# driver_fet.net
KiCad netlist of a schematic drawn in EAGLE
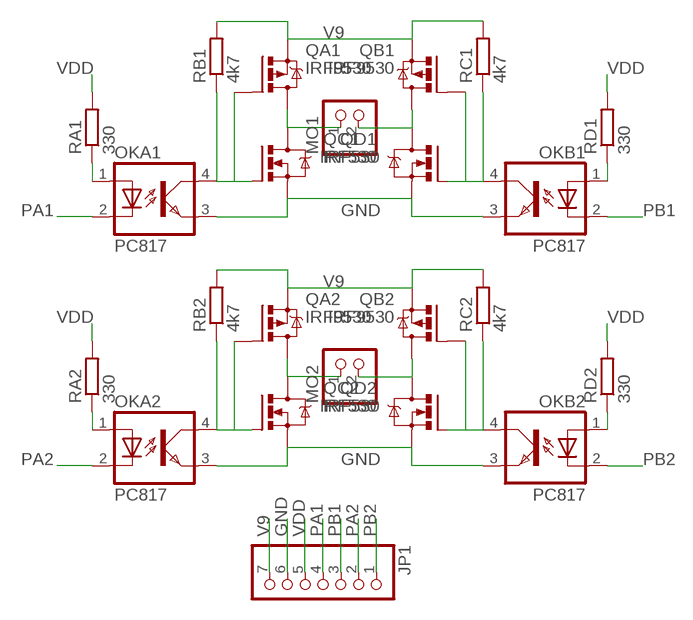
[diagram p0: schematic, sheet 1]

(export (version "E")
  (design (tool "Eeschema 10.0.6"))
  (components
    (comp (ref "JP1")
      (value "PINHD-1X7")
      (footprint "eagle-import:1X07")
      (libsource (lib "eagle-import") (part "PINHD-1X7"))
    )
    (comp (ref "MO1")
      (value "PINHD-1X2")
      (footprint "eagle-import:1X02")
      (libsource (lib "eagle-import") (part "PINHD-1X2"))
    )
    (comp (ref "MO2")
      (value "PINHD-1X2")
      (footprint "eagle-import:1X02")
      (libsource (lib "eagle-import") (part "PINHD-1X2"))
    )
    (comp (ref "OKA1")
      (value "PC817")
      (footprint "eagle-import:DIL04")
      (fields (field (name "MPN") "PC817X4J000F"))
      (libsource (lib "eagle-import") (part "PC817"))
    )
    (comp (ref "OKA2")
      (value "PC817")
      (footprint "eagle-import:DIL04")
      (fields (field (name "MPN") "PC817X4J000F"))
      (libsource (lib "eagle-import") (part "PC817"))
    )
    (comp (ref "OKB1")
      (value "PC817")
      (footprint "eagle-import:DIL04")
      (fields (field (name "MPN") "PC817X4J000F"))
      (libsource (lib "eagle-import") (part "PC817"))
    )
    (comp (ref "OKB2")
      (value "PC817")
      (footprint "eagle-import:DIL04")
      (fields (field (name "MPN") "PC817X4J000F"))
      (libsource (lib "eagle-import") (part "PC817"))
    )
    (comp (ref "QA1")
      (value "IRF9530")
      (footprint "eagle-import:TO220BV")
      (libsource (lib "eagle-import") (part "IRF9530"))
    )
    (comp (ref "QA2")
      (value "IRF9530")
      (footprint "eagle-import:TO220BV")
      (libsource (lib "eagle-import") (part "IRF9530"))
    )
    (comp (ref "QB1")
      (value "IRF9530")
      (footprint "eagle-import:TO220BV")
      (libsource (lib "eagle-import") (part "IRF9530"))
    )
    (comp (ref "QB2")
      (value "IRF9530")
      (footprint "eagle-import:TO220BV")
      (libsource (lib "eagle-import") (part "IRF9530"))
    )
    (comp (ref "QC1")
      (value "IRF530")
      (footprint "eagle-import:TO220BV")
      (libsource (lib "eagle-import") (part "IRF530"))
    )
    (comp (ref "QC2")
      (value "IRF530")
      (footprint "eagle-import:TO220BV")
      (libsource (lib "eagle-import") (part "IRF530"))
    )
    (comp (ref "QD1")
      (value "IRF530")
      (footprint "eagle-import:TO220BV")
      (libsource (lib "eagle-import") (part "IRF530"))
    )
    (comp (ref "QD2")
      (value "IRF530")
      (footprint "eagle-import:TO220BV")
      (libsource (lib "eagle-import") (part "IRF530"))
    )
    (comp (ref "RA1")
      (value "330")
      (footprint "eagle-import:R1206")
      (libsource (lib "eagle-import") (part "R-EU_R1206"))
    )
    (comp (ref "RA2")
      (value "330")
      (footprint "eagle-import:R1206")
      (libsource (lib "eagle-import") (part "R-EU_R1206"))
    )
    (comp (ref "RB1")
      (value "4k7")
      (footprint "eagle-import:R1206")
      (libsource (lib "eagle-import") (part "R-EU_R1206"))
    )
    (comp (ref "RB2")
      (value "4k7")
      (footprint "eagle-import:R1206")
      (libsource (lib "eagle-import") (part "R-EU_R1206"))
    )
    (comp (ref "RC1")
      (value "4k7")
      (footprint "eagle-import:R1206")
      (libsource (lib "eagle-import") (part "R-EU_R1206"))
    )
    (comp (ref "RC2")
      (value "4k7")
      (footprint "eagle-import:R1206")
      (libsource (lib "eagle-import") (part "R-EU_R1206"))
    )
    (comp (ref "RD1")
      (value "330")
      (footprint "eagle-import:R1206")
      (libsource (lib "eagle-import") (part "R-EU_R1206"))
    )
    (comp (ref "RD2")
      (value "330")
      (footprint "eagle-import:R1206")
      (libsource (lib "eagle-import") (part "R-EU_R1206"))
    )
  )
  (nets
    (net (code "1") (name "/GND") (class "Default")
      (node (ref "JP1") (pin "6") (pinfunction "6_6") (pintype "passive"))
      (node (ref "OKA1") (pin "3") (pinfunction "EMIT_3") (pintype "passive"))
      (node (ref "OKA2") (pin "3") (pinfunction "EMIT_3") (pintype "passive"))
      (node (ref "OKB1") (pin "3") (pinfunction "EMIT_3") (pintype "passive"))
      (node (ref "OKB2") (pin "3") (pinfunction "EMIT_3") (pintype "passive"))
      (node (ref "QC1") (pin "S") (pinfunction "S_S") (pintype "passive"))
      (node (ref "QC2") (pin "S") (pinfunction "S_S") (pintype "passive"))
      (node (ref "QD1") (pin "S") (pinfunction "S_S") (pintype "passive"))
      (node (ref "QD2") (pin "S") (pinfunction "S_S") (pintype "passive"))
    )
    (net (code "2") (name "/PA1") (class "Default")
      (node (ref "JP1") (pin "4") (pinfunction "4_4") (pintype "passive"))
      (node (ref "OKA1") (pin "2") (pinfunction "C_2") (pintype "passive"))
    )
    (net (code "3") (name "/PA2") (class "Default")
      (node (ref "JP1") (pin "2") (pinfunction "2_2") (pintype "passive"))
      (node (ref "OKA2") (pin "2") (pinfunction "C_2") (pintype "passive"))
    )
    (net (code "4") (name "/PB1") (class "Default")
      (node (ref "JP1") (pin "3") (pinfunction "3_3") (pintype "passive"))
      (node (ref "OKB1") (pin "2") (pinfunction "C_2") (pintype "passive"))
    )
    (net (code "5") (name "/PB2") (class "Default")
      (node (ref "JP1") (pin "1") (pinfunction "1_1") (pintype "passive"))
      (node (ref "OKB2") (pin "2") (pinfunction "C_2") (pintype "passive"))
    )
    (net (code "6") (name "/V9") (class "Default")
      (node (ref "JP1") (pin "7") (pinfunction "7_7") (pintype "passive"))
      (node (ref "QA1") (pin "S") (pinfunction "S_S") (pintype "passive"))
      (node (ref "QA2") (pin "S") (pinfunction "S_S") (pintype "passive"))
      (node (ref "QB1") (pin "S") (pinfunction "S_S") (pintype "passive"))
      (node (ref "QB2") (pin "S") (pinfunction "S_S") (pintype "passive"))
      (node (ref "RB1") (pin "2") (pinfunction "2_2") (pintype "passive"))
      (node (ref "RB2") (pin "2") (pinfunction "2_2") (pintype "passive"))
      (node (ref "RC1") (pin "2") (pinfunction "2_2") (pintype "passive"))
      (node (ref "RC2") (pin "2") (pinfunction "2_2") (pintype "passive"))
    )
    (net (code "7") (name "/VDD") (class "Default")
      (node (ref "JP1") (pin "5") (pinfunction "5_5") (pintype "passive"))
      (node (ref "RA1") (pin "2") (pinfunction "2_2") (pintype "passive"))
      (node (ref "RA2") (pin "2") (pinfunction "2_2") (pintype "passive"))
      (node (ref "RD1") (pin "2") (pinfunction "2_2") (pintype "passive"))
      (node (ref "RD2") (pin "2") (pinfunction "2_2") (pintype "passive"))
    )
    (net (code "8") (name "Net-(MO1-Pad1)") (class "Default")
      (node (ref "MO1") (pin "1") (pinfunction "1_1") (pintype "passive"))
      (node (ref "QA1") (pin "D") (pinfunction "D_D") (pintype "passive"))
      (node (ref "QC1") (pin "D") (pinfunction "D_D") (pintype "passive"))
    )
    (net (code "9") (name "Net-(MO1-Pad2)") (class "Default")
      (node (ref "MO1") (pin "2") (pinfunction "2_2") (pintype "passive"))
      (node (ref "QB1") (pin "D") (pinfunction "D_D") (pintype "passive"))
      (node (ref "QD1") (pin "D") (pinfunction "D_D") (pintype "passive"))
    )
    (net (code "10") (name "Net-(MO2-Pad1)") (class "Default")
      (node (ref "MO2") (pin "1") (pinfunction "1_1") (pintype "passive"))
      (node (ref "QA2") (pin "D") (pinfunction "D_D") (pintype "passive"))
      (node (ref "QC2") (pin "D") (pinfunction "D_D") (pintype "passive"))
    )
    (net (code "11") (name "Net-(MO2-Pad2)") (class "Default")
      (node (ref "MO2") (pin "2") (pinfunction "2_2") (pintype "passive"))
      (node (ref "QB2") (pin "D") (pinfunction "D_D") (pintype "passive"))
      (node (ref "QD2") (pin "D") (pinfunction "D_D") (pintype "passive"))
    )
    (net (code "12") (name "Net-(OKA1-A)") (class "Default")
      (node (ref "OKA1") (pin "1") (pinfunction "A_1") (pintype "passive"))
      (node (ref "RA1") (pin "1") (pinfunction "1_1") (pintype "passive"))
    )
    (net (code "13") (name "Net-(OKA1-COL)") (class "Default")
      (node (ref "OKA1") (pin "4") (pinfunction "COL_4") (pintype "passive"))
      (node (ref "QA1") (pin "G") (pinfunction "G_G") (pintype "passive"))
      (node (ref "QC1") (pin "G") (pinfunction "G_G") (pintype "passive"))
      (node (ref "RB1") (pin "1") (pinfunction "1_1") (pintype "passive"))
    )
    (net (code "14") (name "Net-(OKA2-A)") (class "Default")
      (node (ref "OKA2") (pin "1") (pinfunction "A_1") (pintype "passive"))
      (node (ref "RA2") (pin "1") (pinfunction "1_1") (pintype "passive"))
    )
    (net (code "15") (name "Net-(OKA2-COL)") (class "Default")
      (node (ref "OKA2") (pin "4") (pinfunction "COL_4") (pintype "passive"))
      (node (ref "QA2") (pin "G") (pinfunction "G_G") (pintype "passive"))
      (node (ref "QC2") (pin "G") (pinfunction "G_G") (pintype "passive"))
      (node (ref "RB2") (pin "1") (pinfunction "1_1") (pintype "passive"))
    )
    (net (code "16") (name "Net-(OKB1-A)") (class "Default")
      (node (ref "OKB1") (pin "1") (pinfunction "A_1") (pintype "passive"))
      (node (ref "RD1") (pin "1") (pinfunction "1_1") (pintype "passive"))
    )
    (net (code "17") (name "Net-(OKB1-COL)") (class "Default")
      (node (ref "OKB1") (pin "4") (pinfunction "COL_4") (pintype "passive"))
      (node (ref "QB1") (pin "G") (pinfunction "G_G") (pintype "passive"))
      (node (ref "QD1") (pin "G") (pinfunction "G_G") (pintype "passive"))
      (node (ref "RC1") (pin "1") (pinfunction "1_1") (pintype "passive"))
    )
    (net (code "18") (name "Net-(OKB2-A)") (class "Default")
      (node (ref "OKB2") (pin "1") (pinfunction "A_1") (pintype "passive"))
      (node (ref "RD2") (pin "1") (pinfunction "1_1") (pintype "passive"))
    )
    (net (code "19") (name "Net-(OKB2-COL)") (class "Default")
      (node (ref "OKB2") (pin "4") (pinfunction "COL_4") (pintype "passive"))
      (node (ref "QB2") (pin "G") (pinfunction "G_G") (pintype "passive"))
      (node (ref "QD2") (pin "G") (pinfunction "G_G") (pintype "passive"))
      (node (ref "RC2") (pin "1") (pinfunction "1_1") (pintype "passive"))
    )
  )
)
